# minisc.net
KiCad netlist of a schematic drawn in EAGLE
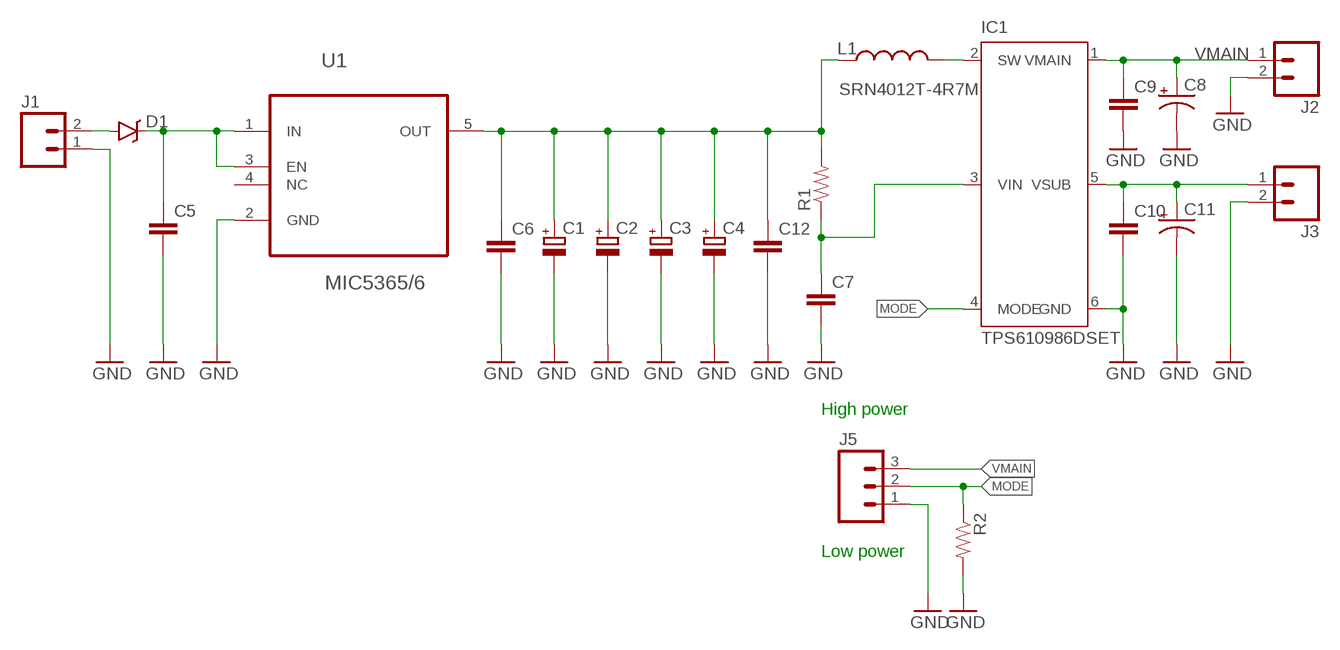
[diagram p0: schematic, sheet 1]

(export (version "E")
  (design (tool "Eeschema 10.0.6"))
  (components
    (comp (ref "C1")
      (value "CPOL-EUE3.5-8")
      (footprint "eagle-import:E3,5-8")
      (libsource (lib "eagle-import") (part "CPOL-EUE3.5-8"))
    )
    (comp (ref "C2")
      (value "CPOL-EUE3.5-8")
      (footprint "eagle-import:E3,5-8")
      (libsource (lib "eagle-import") (part "CPOL-EUE3.5-8"))
    )
    (comp (ref "C3")
      (value "CPOL-EUE3.5-8")
      (footprint "eagle-import:E3,5-8")
      (libsource (lib "eagle-import") (part "CPOL-EUE3.5-8"))
    )
    (comp (ref "C4")
      (value "CPOL-EUE3.5-8")
      (footprint "eagle-import:E3,5-8")
      (libsource (lib "eagle-import") (part "CPOL-EUE3.5-8"))
    )
    (comp (ref "C5")
      (value "CAP0805")
      (footprint "eagle-import:0805")
      (libsource (lib "eagle-import") (part "CAP0805"))
    )
    (comp (ref "C6")
      (value "CAP0805")
      (footprint "eagle-import:0805")
      (libsource (lib "eagle-import") (part "CAP0805"))
    )
    (comp (ref "C7")
      (value "CAP0805")
      (footprint "eagle-import:0805")
      (libsource (lib "eagle-import") (part "CAP0805"))
    )
    (comp (ref "C8")
      (value "CAP_POL3528-KIT")
      (footprint "eagle-import:EIA3528-KIT")
      (libsource (lib "eagle-import") (part "CAP_POL3528-KIT"))
    )
    (comp (ref "C9")
      (value "CAP0805")
      (footprint "eagle-import:0805")
      (libsource (lib "eagle-import") (part "CAP0805"))
    )
    (comp (ref "C10")
      (value "CAP0805")
      (footprint "eagle-import:0805")
      (libsource (lib "eagle-import") (part "CAP0805"))
    )
    (comp (ref "C11")
      (value "CAP_POL3528-KIT")
      (footprint "eagle-import:EIA3528-KIT")
      (libsource (lib "eagle-import") (part "CAP_POL3528-KIT"))
    )
    (comp (ref "C12")
      (value "CAP0805")
      (footprint "eagle-import:0805")
      (libsource (lib "eagle-import") (part "CAP0805"))
    )
    (comp (ref "D1")
      (value "DIODE-SCHOTTKY-BAT20J")
      (footprint "eagle-import:SOD-323")
      (libsource (lib "eagle-import") (part "DIODE-SCHOTTKY-BAT20J"))
    )
    (comp (ref "IC1")
      (value "TPS610986DSET")
      (footprint "eagle-import:WSON-6")
      (libsource (lib "eagle-import") (part "TPS610985DSET"))
    )
    (comp (ref "J1")
      (value "M02PTH")
      (footprint "eagle-import:1X02")
      (libsource (lib "eagle-import") (part "M02PTH"))
    )
    (comp (ref "J2")
      (value "M02PTH")
      (footprint "eagle-import:1X02")
      (libsource (lib "eagle-import") (part "M02PTH"))
    )
    (comp (ref "J3")
      (value "M02PTH")
      (footprint "eagle-import:1X02")
      (libsource (lib "eagle-import") (part "M02PTH"))
    )
    (comp (ref "J5")
      (value "M03PTH")
      (footprint "eagle-import:1X03")
      (libsource (lib "eagle-import") (part "M03PTH"))
    )
    (comp (ref "L1")
      (value "SRN4012T-4R7M")
      (footprint "eagle-import:CR54")
      (libsource (lib "eagle-import") (part "INDUCTORCR54-3.3UH"))
    )
    (comp (ref "R1")
      (value "RESISTOR0805-RES")
      (footprint "eagle-import:0805")
      (libsource (lib "eagle-import") (part "RESISTOR0805-RES"))
    )
    (comp (ref "R2")
      (value "RESISTOR0805-RES")
      (footprint "eagle-import:0805")
      (libsource (lib "eagle-import") (part "RESISTOR0805-RES"))
    )
    (comp (ref "U1")
      (value "MIC5365/6")
      (footprint "eagle-import:SC-70-5")
      (fields (field (name "MPN") "MIC5365"))
      (libsource (lib "eagle-import") (part "MIC5365/6"))
    )
  )
  (nets
    (net (code "1") (name "GND") (class "Default")
      (node (ref "C1") (pin "-") (pinfunction "-_-") (pintype "passive"))
      (node (ref "C10") (pin "2") (pinfunction "2_2") (pintype "passive"))
      (node (ref "C11") (pin "C") (pinfunction "-_C") (pintype "passive"))
      (node (ref "C12") (pin "2") (pinfunction "2_2") (pintype "passive"))
      (node (ref "C2") (pin "-") (pinfunction "-_-") (pintype "passive"))
      (node (ref "C3") (pin "-") (pinfunction "-_-") (pintype "passive"))
      (node (ref "C4") (pin "-") (pinfunction "-_-") (pintype "passive"))
      (node (ref "C5") (pin "2") (pinfunction "2_2") (pintype "passive"))
      (node (ref "C6") (pin "2") (pinfunction "2_2") (pintype "passive"))
      (node (ref "C7") (pin "2") (pinfunction "2_2") (pintype "passive"))
      (node (ref "C8") (pin "C") (pinfunction "-_C") (pintype "passive"))
      (node (ref "C9") (pin "2") (pinfunction "2_2") (pintype "passive"))
      (node (ref "IC1") (pin "6") (pinfunction "GND_6") (pintype "power_in"))
      (node (ref "J1") (pin "1") (pinfunction "1_1") (pintype "passive"))
      (node (ref "J2") (pin "2") (pinfunction "2_2") (pintype "passive"))
      (node (ref "J3") (pin "2") (pinfunction "2_2") (pintype "passive"))
      (node (ref "J5") (pin "1") (pinfunction "1_1") (pintype "passive"))
      (node (ref "R2") (pin "2") (pinfunction "2_2") (pintype "passive"))
      (node (ref "U1") (pin "2") (pinfunction "GND_2") (pintype "passive"))
    )
    (net (code "2") (name "MODE") (class "Default")
      (node (ref "IC1") (pin "4") (pinfunction "MODE_4") (pintype "passive"))
      (node (ref "J5") (pin "2") (pinfunction "2_2") (pintype "passive"))
      (node (ref "R2") (pin "1") (pinfunction "1_1") (pintype "passive"))
    )
    (net (code "3") (name "Net-(C11-+)") (class "Default")
      (node (ref "C10") (pin "1") (pinfunction "1_1") (pintype "passive"))
      (node (ref "C11") (pin "A") (pinfunction "+_A") (pintype "passive"))
      (node (ref "IC1") (pin "5") (pinfunction "VSUB_5") (pintype "output"))
      (node (ref "J3") (pin "1") (pinfunction "1_1") (pintype "passive"))
    )
    (net (code "4") (name "Net-(D1-PadA)") (class "Default")
      (node (ref "D1") (pin "A") (pinfunction "A_A") (pintype "passive"))
      (node (ref "J1") (pin "2") (pinfunction "2_2") (pintype "passive"))
    )
    (net (code "5") (name "Net-(IC1-SW)") (class "Default")
      (node (ref "IC1") (pin "2") (pinfunction "SW_2") (pintype "output"))
      (node (ref "L1") (pin "P$2") (pinfunction "2_P$2") (pintype "passive"))
    )
    (net (code "6") (name "Net-(IC1-VIN)") (class "Default")
      (node (ref "C7") (pin "1") (pinfunction "1_1") (pintype "passive"))
      (node (ref "IC1") (pin "3") (pinfunction "VIN_3") (pintype "input"))
      (node (ref "R1") (pin "1") (pinfunction "1_1") (pintype "passive"))
    )
    (net (code "7") (name "Net-(L1-1)") (class "Default")
      (node (ref "C1") (pin "+") (pinfunction "+_+") (pintype "passive"))
      (node (ref "C12") (pin "1") (pinfunction "1_1") (pintype "passive"))
      (node (ref "C2") (pin "+") (pinfunction "+_+") (pintype "passive"))
      (node (ref "C3") (pin "+") (pinfunction "+_+") (pintype "passive"))
      (node (ref "C4") (pin "+") (pinfunction "+_+") (pintype "passive"))
      (node (ref "C6") (pin "1") (pinfunction "1_1") (pintype "passive"))
      (node (ref "L1") (pin "P$1") (pinfunction "1_P$1") (pintype "passive"))
      (node (ref "R1") (pin "2") (pinfunction "2_2") (pintype "passive"))
      (node (ref "U1") (pin "5") (pinfunction "OUT_5") (pintype "output"))
    )
    (net (code "8") (name "Net-(U1-EN)") (class "Default")
      (node (ref "C5") (pin "1") (pinfunction "1_1") (pintype "passive"))
      (node (ref "D1") (pin "C") (pinfunction "C_C") (pintype "passive"))
      (node (ref "U1") (pin "1") (pinfunction "IN_1") (pintype "input"))
      (node (ref "U1") (pin "3") (pinfunction "EN_3") (pintype "input"))
    )
    (net (code "9") (name "VMAIN") (class "Default")
      (node (ref "C8") (pin "A") (pinfunction "+_A") (pintype "passive"))
      (node (ref "C9") (pin "1") (pinfunction "1_1") (pintype "passive"))
      (node (ref "IC1") (pin "1") (pinfunction "VMAIN_1") (pintype "input"))
      (node (ref "J2") (pin "1") (pinfunction "1_1") (pintype "passive"))
      (node (ref "J5") (pin "3") (pinfunction "3_3") (pintype "passive"))
    )
    (net (code "10") (name "unconnected-(U1-NC-Pad4)") (class "Default")
      (node (ref "U1") (pin "4") (pinfunction "NC_4") (pintype "input"))
    )
  )
)
